# final.net
KiCad netlist of a schematic drawn in EasyEDA Pro
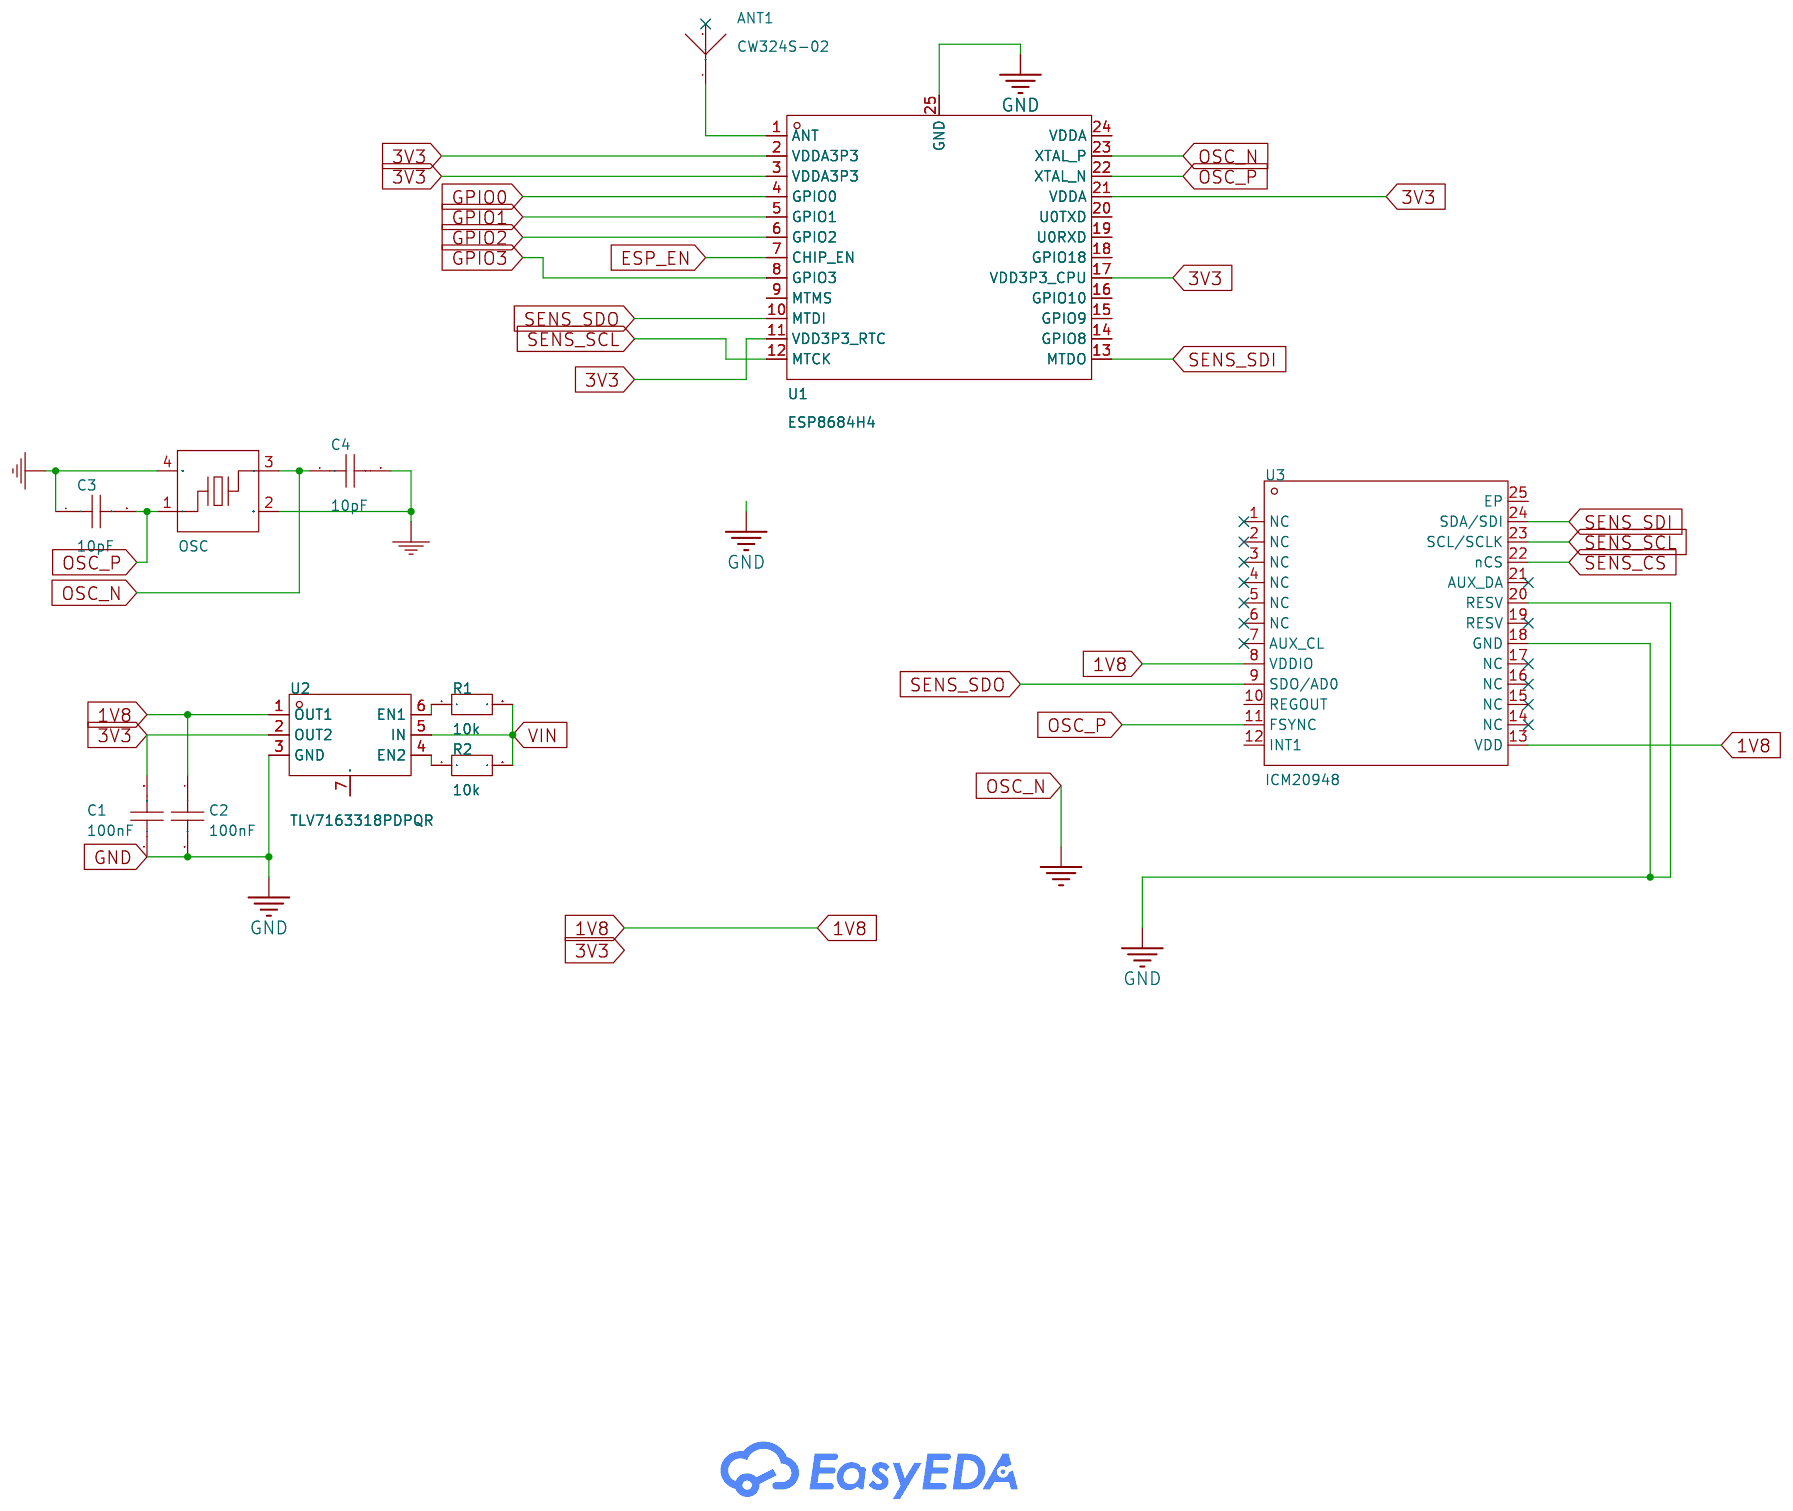
[diagram p0: schematic sheet]

(export (version "E")
  (design (tool "Eeschema 10.0.6"))
  (components
    (comp (ref "ANT1")
      (value "CW324S-02")
      (footprint "easyedapro:ANT-SMD_L3.2-W1.6_CW324S-01")
      (fields (field (name "Manufacturer") "LXC(连兴创)"))
      (libsource (lib "easyedapro") (part "CW324S-02"))
    )
    (comp (ref "C1")
      (value "100nF")
      (footprint "easyedapro:C0201")
      (description "Capacitance:100nF Tolerance:±10% Tolerance:±10% Voltage Rating:10V Temperature Coefficient:X5R")
      (fields
        (field (name "Manufacturer Part") "C0201X5R104K100NTA")
        (field (name "Manufacturer") "EYANG(宇阳科技)")
      )
      (libsource (lib "easyedapro") (part "C0201X5R104K100NTA"))
    )
    (comp (ref "C2")
      (value "100nF")
      (footprint "easyedapro:C0201")
      (description "Capacitance:100nF Tolerance:±10% Tolerance:±10% Voltage Rating:10V Temperature Coefficient:X5R")
      (fields
        (field (name "Manufacturer Part") "C0201X5R104K100NTA")
        (field (name "Manufacturer") "EYANG(宇阳科技)")
      )
      (libsource (lib "easyedapro") (part "C0201X5R104K100NTA"))
    )
    (comp (ref "C3")
      (value "10pF")
      (footprint "easyedapro:C0201")
      (description "Capacitance:100nF Tolerance:±10% Tolerance:±10% Voltage Rating:10V Temperature Coefficient:X5R")
      (fields
        (field (name "Manufacturer Part") "C0201X5R104K100NTA")
        (field (name "Manufacturer") "EYANG(宇阳科技)")
      )
      (libsource (lib "easyedapro") (part "C0201X5R104K100NTA"))
    )
    (comp (ref "C4")
      (value "10pF")
      (footprint "easyedapro:C0201")
      (description "Capacitance:100nF Tolerance:±10% Tolerance:±10% Voltage Rating:10V Temperature Coefficient:X5R")
      (fields
        (field (name "Manufacturer Part") "C0201X5R104K100NTA")
        (field (name "Manufacturer") "EYANG(宇阳科技)")
      )
      (libsource (lib "easyedapro") (part "C0201X5R104K100NTA"))
    )
    (comp (ref "R1")
      (value "10k")
      (footprint "easyedapro:R0201")
      (fields
        (field (name "Manufacturer Part") "CRCW0201174KFKED")
        (field (name "Manufacturer") "VISHAY(威世)")
      )
      (libsource (lib "easyedapro") (part "CRCW0201174KFKED"))
    )
    (comp (ref "R2")
      (value "10k")
      (footprint "easyedapro:R0201")
      (fields
        (field (name "Manufacturer Part") "CRCW0201174KFKED")
        (field (name "Manufacturer") "VISHAY(威世)")
      )
      (libsource (lib "easyedapro") (part "CRCW0201174KFKED"))
    )
    (comp (ref "U1")
      (value "ESP8684H4")
      (footprint "easyedapro:QFN-24_L4.0-W4.0-P0.50-TL-EP2.8")
      (fields (field (name "Manufacturer") "ESPRESSIF(乐鑫)"))
      (libsource (lib "easyedapro") (part "ESP8684H4"))
    )
    (comp (ref "U2")
      (value "TLV7163318PDPQR")
      (footprint "easyedapro:XDFN-6_L1.2-W1.2-P0.40-BL-EP")
      (fields (field (name "Manufacturer") "TI(德州仪器)"))
      (libsource (lib "easyedapro") (part "TLV7163318PDPQR"))
    )
    (comp (ref "U3")
      (value "ICM20948")
      (footprint "easyedapro:QFN-24_L3.0-W3.0-P0.40-BL-EP")
      (libsource (lib "easyedapro") (part "ICM20948"))
    )
    (comp (ref "X1")
      (value "OSC")
      (footprint "easyedapro:CRYSTAL-SMD_4P-L1.6-W1.2-BL")
      (fields
        (field (name "Manufacturer Part") "SX0B40.000F1010F30")
        (field (name "Manufacturer") "SCTF(星通时频)")
        (field (name "Contributor") "lcsc")
      )
      (libsource (lib "easyedapro") (part "40MHz"))
    )
  )
  (nets
    (net (code "1") (name "1V8") (class "Default")
      (node (ref "C2") (pin "1") (pinfunction "1_1") (pintype "unspecified"))
      (node (ref "U2") (pin "1") (pinfunction "OUT1_1") (pintype "unspecified"))
      (node (ref "U3") (pin "13") (pinfunction "VDD_13") (pintype "input"))
      (node (ref "U3") (pin "8") (pinfunction "VDDIO_8") (pintype "input"))
    )
    (net (code "2") (name "3V3") (class "Default")
      (node (ref "C1") (pin "2") (pinfunction "2_2") (pintype "unspecified"))
      (node (ref "U1") (pin "11") (pinfunction "VDD3P3_RTC_11") (pintype "unspecified"))
      (node (ref "U1") (pin "17") (pinfunction "VDD3P3_CPU_17") (pintype "unspecified"))
      (node (ref "U1") (pin "2") (pinfunction "VDDA3P3_2") (pintype "unspecified"))
      (node (ref "U1") (pin "21") (pinfunction "VDDA_21") (pintype "unspecified"))
      (node (ref "U1") (pin "3") (pinfunction "VDDA3P3_3") (pintype "unspecified"))
      (node (ref "U2") (pin "2") (pinfunction "OUT2_2") (pintype "unspecified"))
    )
    (net (code "3") (name "ESP_EN") (class "Default")
      (node (ref "U1") (pin "7") (pinfunction "CHIP_EN_7") (pintype "unspecified"))
    )
    (net (code "4") (name "GND") (class "Default")
      (node (ref "C1") (pin "1") (pinfunction "1_1") (pintype "unspecified"))
      (node (ref "C2") (pin "2") (pinfunction "2_2") (pintype "unspecified"))
      (node (ref "C3") (pin "1") (pinfunction "1_1") (pintype "unspecified"))
      (node (ref "C4") (pin "2") (pinfunction "2_2") (pintype "unspecified"))
      (node (ref "U1") (pin "25") (pinfunction "GND_25") (pintype "unspecified"))
      (node (ref "U2") (pin "3") (pinfunction "GND_3") (pintype "unspecified"))
      (node (ref "U3") (pin "18") (pinfunction "GND_18") (pintype "input"))
      (node (ref "U3") (pin "20") (pinfunction "RESV_20") (pintype "input"))
      (node (ref "X1") (pin "2") (pinfunction "GND_2") (pintype "input"))
      (node (ref "X1") (pin "4") (pinfunction "GND_4") (pintype "input"))
    )
    (net (code "5") (name "GPIO0") (class "Default")
      (node (ref "U1") (pin "4") (pinfunction "GPIO0_4") (pintype "unspecified"))
    )
    (net (code "6") (name "GPIO1") (class "Default")
      (node (ref "U1") (pin "5") (pinfunction "GPIO1_5") (pintype "unspecified"))
    )
    (net (code "7") (name "GPIO2") (class "Default")
      (node (ref "U1") (pin "6") (pinfunction "GPIO2_6") (pintype "unspecified"))
    )
    (net (code "8") (name "GPIO3") (class "Default")
      (node (ref "U1") (pin "8") (pinfunction "GPIO3_8") (pintype "unspecified"))
    )
    (net (code "9") (name "Net-(ANT1-ANT)") (class "Default")
      (node (ref "ANT1") (pin "1") (pinfunction "ANT_1") (pintype "unspecified"))
      (node (ref "U1") (pin "1") (pinfunction "ANT_1") (pintype "unspecified"))
    )
    (net (code "10") (name "Net-(U2-EN1)") (class "Default")
      (node (ref "R1") (pin "1") (pinfunction "1_1") (pintype "unspecified"))
      (node (ref "U2") (pin "6") (pinfunction "EN1_6") (pintype "unspecified"))
    )
    (net (code "11") (name "Net-(U2-EN2)") (class "Default")
      (node (ref "R2") (pin "1") (pinfunction "1_1") (pintype "unspecified"))
      (node (ref "U2") (pin "4") (pinfunction "EN2_4") (pintype "unspecified"))
    )
    (net (code "12") (name "OSC_N") (class "Default")
      (node (ref "C4") (pin "1") (pinfunction "1_1") (pintype "unspecified"))
      (node (ref "U1") (pin "23") (pinfunction "XTAL_P_23") (pintype "unspecified"))
      (node (ref "X1") (pin "3") (pinfunction "3_3") (pintype "input"))
    )
    (net (code "13") (name "OSC_P") (class "Default")
      (node (ref "C3") (pin "2") (pinfunction "2_2") (pintype "unspecified"))
      (node (ref "U1") (pin "22") (pinfunction "XTAL_N_22") (pintype "unspecified"))
      (node (ref "U3") (pin "11") (pinfunction "FSYNC_11") (pintype "input"))
      (node (ref "X1") (pin "1") (pinfunction "1_1") (pintype "input"))
    )
    (net (code "14") (name "SENS_CS") (class "Default")
      (node (ref "U3") (pin "22") (pinfunction "nCS_22") (pintype "input"))
    )
    (net (code "15") (name "SENS_SCL") (class "Default")
      (node (ref "U1") (pin "12") (pinfunction "MTCK_12") (pintype "unspecified"))
      (node (ref "U3") (pin "23") (pinfunction "SCL/SCLK_23") (pintype "input"))
    )
    (net (code "16") (name "SENS_SDI") (class "Default")
      (node (ref "U1") (pin "13") (pinfunction "MTDO_13") (pintype "unspecified"))
      (node (ref "U3") (pin "24") (pinfunction "SDA/SDI_24") (pintype "input"))
    )
    (net (code "17") (name "SENS_SDO") (class "Default")
      (node (ref "U1") (pin "10") (pinfunction "MTDI_10") (pintype "unspecified"))
      (node (ref "U3") (pin "9") (pinfunction "SDO/AD0_9") (pintype "input"))
    )
    (net (code "18") (name "VIN") (class "Default")
      (node (ref "R1") (pin "2") (pinfunction "2_2") (pintype "unspecified"))
      (node (ref "R2") (pin "2") (pinfunction "2_2") (pintype "unspecified"))
      (node (ref "U2") (pin "5") (pinfunction "IN_5") (pintype "unspecified"))
    )
    (net (code "19") (name "unconnected-(ANT1-Pad2)") (class "Default")
      (node (ref "ANT1") (pin "2") (pinfunction "2_2") (pintype "unspecified+no_connect"))
    )
    (net (code "20") (name "unconnected-(U1-GPIO8-Pad14)") (class "Default")
      (node (ref "U1") (pin "14") (pinfunction "GPIO8_14") (pintype "unspecified"))
    )
    (net (code "21") (name "unconnected-(U1-GPIO9-Pad15)") (class "Default")
      (node (ref "U1") (pin "15") (pinfunction "GPIO9_15") (pintype "unspecified"))
    )
    (net (code "22") (name "unconnected-(U1-GPIO10-Pad16)") (class "Default")
      (node (ref "U1") (pin "16") (pinfunction "GPIO10_16") (pintype "unspecified"))
    )
    (net (code "23") (name "unconnected-(U1-GPIO18-Pad18)") (class "Default")
      (node (ref "U1") (pin "18") (pinfunction "GPIO18_18") (pintype "unspecified"))
    )
    (net (code "24") (name "unconnected-(U1-MTMS-Pad9)") (class "Default")
      (node (ref "U1") (pin "9") (pinfunction "MTMS_9") (pintype "unspecified"))
    )
    (net (code "25") (name "unconnected-(U1-U0RXD-Pad19)") (class "Default")
      (node (ref "U1") (pin "19") (pinfunction "U0RXD_19") (pintype "unspecified"))
    )
    (net (code "26") (name "unconnected-(U1-U0TXD-Pad20)") (class "Default")
      (node (ref "U1") (pin "20") (pinfunction "U0TXD_20") (pintype "unspecified"))
    )
    (net (code "27") (name "unconnected-(U1-VDDA-Pad24)") (class "Default")
      (node (ref "U1") (pin "24") (pinfunction "VDDA_24") (pintype "unspecified"))
    )
    (net (code "28") (name "unconnected-(U2-EP-Pad7)") (class "Default")
      (node (ref "U2") (pin "7") (pinfunction "EP_7") (pintype "unspecified"))
    )
    (net (code "29") (name "unconnected-(U3-AUX_CL-Pad7)") (class "Default")
      (node (ref "U3") (pin "7") (pinfunction "AUX_CL_7") (pintype "input+no_connect"))
    )
    (net (code "30") (name "unconnected-(U3-AUX_DA-Pad21)") (class "Default")
      (node (ref "U3") (pin "21") (pinfunction "AUX_DA_21") (pintype "input+no_connect"))
    )
    (net (code "31") (name "unconnected-(U3-EP-Pad25)") (class "Default")
      (node (ref "U3") (pin "25") (pinfunction "EP_25") (pintype "input"))
    )
    (net (code "32") (name "unconnected-(U3-INT1-Pad12)") (class "Default")
      (node (ref "U3") (pin "12") (pinfunction "INT1_12") (pintype "input"))
    )
    (net (code "33") (name "unconnected-(U3-NC-Pad1)") (class "Default")
      (node (ref "U3") (pin "1") (pinfunction "NC_1") (pintype "input+no_connect"))
    )
    (net (code "34") (name "unconnected-(U3-NC-Pad2)") (class "Default")
      (node (ref "U3") (pin "2") (pinfunction "NC_2") (pintype "input+no_connect"))
    )
    (net (code "35") (name "unconnected-(U3-NC-Pad3)") (class "Default")
      (node (ref "U3") (pin "3") (pinfunction "NC_3") (pintype "input+no_connect"))
    )
    (net (code "36") (name "unconnected-(U3-NC-Pad4)") (class "Default")
      (node (ref "U3") (pin "4") (pinfunction "NC_4") (pintype "input+no_connect"))
    )
    (net (code "37") (name "unconnected-(U3-NC-Pad5)") (class "Default")
      (node (ref "U3") (pin "5") (pinfunction "NC_5") (pintype "input+no_connect"))
    )
    (net (code "38") (name "unconnected-(U3-NC-Pad6)") (class "Default")
      (node (ref "U3") (pin "6") (pinfunction "NC_6") (pintype "input+no_connect"))
    )
    (net (code "39") (name "unconnected-(U3-NC-Pad14)") (class "Default")
      (node (ref "U3") (pin "14") (pinfunction "NC_14") (pintype "input+no_connect"))
    )
    (net (code "40") (name "unconnected-(U3-NC-Pad15)") (class "Default")
      (node (ref "U3") (pin "15") (pinfunction "NC_15") (pintype "input+no_connect"))
    )
    (net (code "41") (name "unconnected-(U3-NC-Pad16)") (class "Default")
      (node (ref "U3") (pin "16") (pinfunction "NC_16") (pintype "input+no_connect"))
    )
    (net (code "42") (name "unconnected-(U3-NC-Pad17)") (class "Default")
      (node (ref "U3") (pin "17") (pinfunction "NC_17") (pintype "input+no_connect"))
    )
    (net (code "43") (name "unconnected-(U3-REGOUT-Pad10)") (class "Default")
      (node (ref "U3") (pin "10") (pinfunction "REGOUT_10") (pintype "input"))
    )
    (net (code "44") (name "unconnected-(U3-RESV-Pad19)") (class "Default")
      (node (ref "U3") (pin "19") (pinfunction "RESV_19") (pintype "input+no_connect"))
    )
  )
)
